# Power.net
KiCad netlist of a schematic drawn in Altium Designer
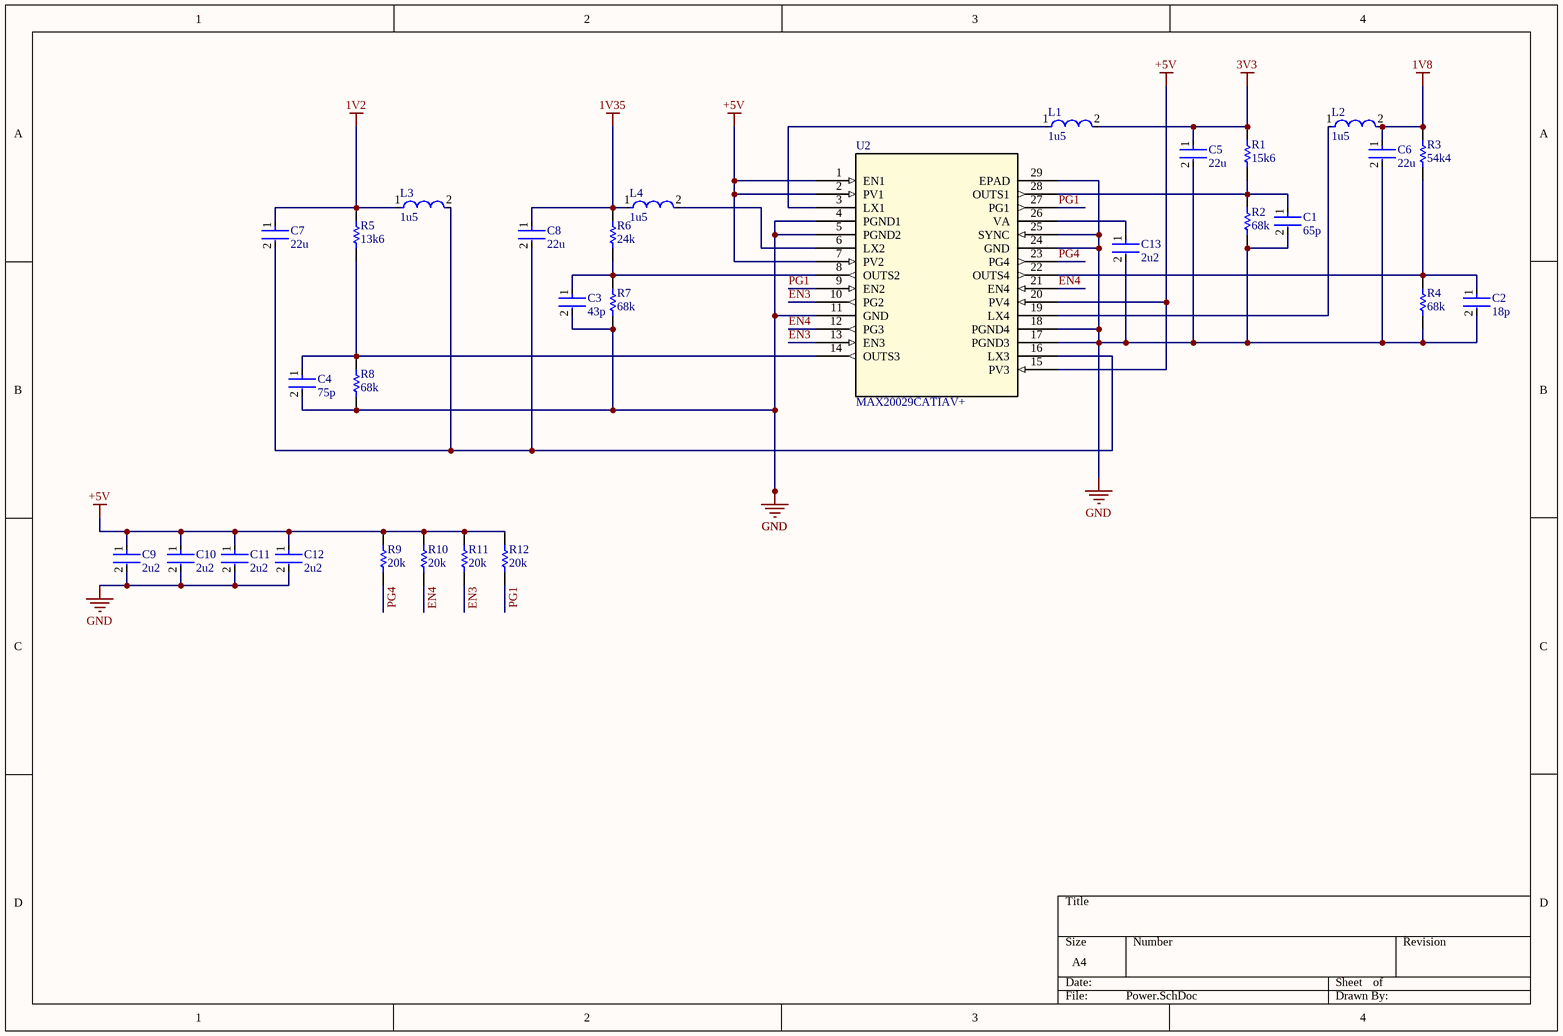
[diagram p0: Power.SchDoc]

(export (version "E")
  (design (tool "Eeschema 10.0.6"))
  (components
    (comp (ref "C1")
      (value "65p")
      (footprint "FP-C0603C-CF-MFG")
      (description "CAP CER 0.1UF 50V X7R 0603")
      (fields (field (name "TOLERANCE") "0.1") (field (name "MANUFACTURER") "KEMET"))
      (libsource (lib "Altium Content Vault") (part "b4654b650e69147ec39a6b967a45e02"))
    )
    (comp (ref "C2")
      (value "18p")
      (footprint "FP-C0603C-CF-MFG")
      (description "CAP CER 0.1UF 50V X7R 0603")
      (fields (field (name "TOLERANCE") "0.1") (field (name "MANUFACTURER") "KEMET"))
      (libsource (lib "Altium Content Vault") (part "b4654b650e69147ec39a6b967a45e02"))
    )
    (comp (ref "C3")
      (value "43p")
      (footprint "FP-C0603C-CF-MFG")
      (description "CAP CER 0.1UF 50V X7R 0603")
      (fields (field (name "TOLERANCE") "0.1") (field (name "MANUFACTURER") "KEMET"))
      (libsource (lib "Altium Content Vault") (part "b4654b650e69147ec39a6b967a45e02"))
    )
    (comp (ref "C4")
      (value "75p")
      (footprint "FP-C0603C-CF-MFG")
      (description "CAP CER 0.1UF 50V X7R 0603")
      (fields (field (name "TOLERANCE") "0.1") (field (name "MANUFACTURER") "KEMET"))
      (libsource (lib "Altium Content Vault") (part "b4654b650e69147ec39a6b967a45e02"))
    )
    (comp (ref "C5")
      (value "22u")
      (footprint "FP-CC0805-0_85-MFG")
      (description "CAP CER 0.1UF 50V X7R 0805")
      (fields (field (name "TOLERANCE") "0.1") (field (name "MANUFACTURER PART NUMBER") "CC0805KRX7R9BB104"))
      (libsource (lib "Altium Content Vault") (part "11868f565c42a9108669ba33697ecf6"))
    )
    (comp (ref "C6")
      (value "22u")
      (footprint "FP-CC0805-0_85-MFG")
      (description "CAP CER 0.1UF 50V X7R 0805")
      (fields (field (name "TOLERANCE") "0.1") (field (name "MANUFACTURER PART NUMBER") "CC0805KRX7R9BB104"))
      (libsource (lib "Altium Content Vault") (part "11868f565c42a9108669ba33697ecf6"))
    )
    (comp (ref "C7")
      (value "22u")
      (footprint "FP-CC0805-0_85-MFG")
      (description "CAP CER 0.1UF 50V X7R 0805")
      (fields (field (name "TOLERANCE") "0.1") (field (name "MANUFACTURER PART NUMBER") "CC0805KRX7R9BB104"))
      (libsource (lib "Altium Content Vault") (part "11868f565c42a9108669ba33697ecf6"))
    )
    (comp (ref "C8")
      (value "22u")
      (footprint "FP-CC0805-0_85-MFG")
      (description "CAP CER 0.1UF 50V X7R 0805")
      (fields (field (name "TOLERANCE") "0.1") (field (name "MANUFACTURER PART NUMBER") "CC0805KRX7R9BB104"))
      (libsource (lib "Altium Content Vault") (part "11868f565c42a9108669ba33697ecf6"))
    )
    (comp (ref "C9")
      (value "2u2")
      (footprint "FP-CC0805-0_85-MFG")
      (description "CAP CER 0.1UF 50V X7R 0805")
      (fields (field (name "TOLERANCE") "0.1") (field (name "MANUFACTURER PART NUMBER") "CC0805KRX7R9BB104"))
      (libsource (lib "Altium Content Vault") (part "11868f565c42a9108669ba33697ecf6"))
    )
    (comp (ref "C10")
      (value "2u2")
      (footprint "FP-CC0805-0_85-MFG")
      (description "CAP CER 0.1UF 50V X7R 0805")
      (fields (field (name "TOLERANCE") "0.1") (field (name "MANUFACTURER PART NUMBER") "CC0805KRX7R9BB104"))
      (libsource (lib "Altium Content Vault") (part "11868f565c42a9108669ba33697ecf6"))
    )
    (comp (ref "C11")
      (value "2u2")
      (footprint "FP-CC0805-0_85-MFG")
      (description "CAP CER 0.1UF 50V X7R 0805")
      (fields (field (name "TOLERANCE") "0.1") (field (name "MANUFACTURER PART NUMBER") "CC0805KRX7R9BB104"))
      (libsource (lib "Altium Content Vault") (part "11868f565c42a9108669ba33697ecf6"))
    )
    (comp (ref "C12")
      (value "2u2")
      (footprint "FP-CC0805-0_85-MFG")
      (description "CAP CER 0.1UF 50V X7R 0805")
      (fields (field (name "TOLERANCE") "0.1") (field (name "MANUFACTURER PART NUMBER") "CC0805KRX7R9BB104"))
      (libsource (lib "Altium Content Vault") (part "11868f565c42a9108669ba33697ecf6"))
    )
    (comp (ref "C13")
      (value "2u2")
      (footprint "FP-CC0805-0_85-MFG")
      (description "CAP CER 0.1UF 50V X7R 0805")
      (fields (field (name "TOLERANCE") "0.1") (field (name "MANUFACTURER PART NUMBER") "CC0805KRX7R9BB104"))
      (libsource (lib "Altium Content Vault") (part "11868f565c42a9108669ba33697ecf6"))
    )
    (comp (ref "L1")
      (value "1u5")
      (footprint "FP-LQM2HPN_G0-IPC_A")
      (description "FIXED IND 1UH 1.6A 55 MOHM SMD")
      (fields (field (name "TOLERANCE") "20%"))
      (libsource (lib "Altium Content Vault") (part "725321dda6339637d4d059423bc1c3c"))
    )
    (comp (ref "L2")
      (value "1u5")
      (footprint "FP-LQM2HPN_G0-IPC_A")
      (description "FIXED IND 1UH 1.6A 55 MOHM SMD")
      (fields (field (name "TOLERANCE") "20%"))
      (libsource (lib "Altium Content Vault") (part "725321dda6339637d4d059423bc1c3c"))
    )
    (comp (ref "L3")
      (value "1u5")
      (footprint "FP-LQM2HPN_G0-IPC_A")
      (description "FIXED IND 1UH 1.6A 55 MOHM SMD")
      (fields (field (name "TOLERANCE") "20%"))
      (libsource (lib "Altium Content Vault") (part "725321dda6339637d4d059423bc1c3c"))
    )
    (comp (ref "L4")
      (value "1u5")
      (footprint "FP-LQM2HPN_G0-IPC_A")
      (description "FIXED IND 1UH 1.6A 55 MOHM SMD")
      (fields (field (name "TOLERANCE") "20%"))
      (libsource (lib "Altium Content Vault") (part "725321dda6339637d4d059423bc1c3c"))
    )
    (comp (ref "R1")
      (value "15k6")
      (footprint "RESC1609X50X30NL8T20")
      (description "Chip Resistor, 10 KOhm, +/- 1%, 100 mW, -55 to 155 degC, 0603 (1608 Metric), RoHS, Tape and Reel")
      (fields (field (name "MANUFACTURER") "Vishay Semiconductor"))
      (libsource (lib "Altium Content Vault") (part "RES-2"))
    )
    (comp (ref "R2")
      (value "68k")
      (footprint "RESC1609X50X30NL8T20")
      (description "Chip Resistor, 10 KOhm, +/- 1%, 100 mW, -55 to 155 degC, 0603 (1608 Metric), RoHS, Tape and Reel")
      (fields (field (name "MANUFACTURER") "Vishay Semiconductor"))
      (libsource (lib "Altium Content Vault") (part "RES-2"))
    )
    (comp (ref "R3")
      (value "54k4")
      (footprint "RESC1609X50X30NL8T20")
      (description "Chip Resistor, 10 KOhm, +/- 1%, 100 mW, -55 to 155 degC, 0603 (1608 Metric), RoHS, Tape and Reel")
      (fields (field (name "MANUFACTURER") "Vishay Semiconductor"))
      (libsource (lib "Altium Content Vault") (part "RES-2"))
    )
    (comp (ref "R4")
      (value "68k")
      (footprint "RESC1609X50X30NL8T20")
      (description "Chip Resistor, 10 KOhm, +/- 1%, 100 mW, -55 to 155 degC, 0603 (1608 Metric), RoHS, Tape and Reel")
      (fields (field (name "MANUFACTURER") "Vishay Semiconductor"))
      (libsource (lib "Altium Content Vault") (part "RES-2"))
    )
    (comp (ref "R5")
      (value "13k6")
      (footprint "RESC1609X50X30NL8T20")
      (description "Chip Resistor, 10 KOhm, +/- 1%, 100 mW, -55 to 155 degC, 0603 (1608 Metric), RoHS, Tape and Reel")
      (fields (field (name "MANUFACTURER") "Vishay Semiconductor"))
      (libsource (lib "Altium Content Vault") (part "RES-2"))
    )
    (comp (ref "R6")
      (value "24k")
      (footprint "RESC1609X50X30NL8T20")
      (description "Chip Resistor, 10 KOhm, +/- 1%, 100 mW, -55 to 155 degC, 0603 (1608 Metric), RoHS, Tape and Reel")
      (fields (field (name "MANUFACTURER") "Vishay Semiconductor"))
      (libsource (lib "Altium Content Vault") (part "RES-2"))
    )
    (comp (ref "R7")
      (value "68k")
      (footprint "RESC1609X50X30NL8T20")
      (description "Chip Resistor, 10 KOhm, +/- 1%, 100 mW, -55 to 155 degC, 0603 (1608 Metric), RoHS, Tape and Reel")
      (fields (field (name "MANUFACTURER") "Vishay Semiconductor"))
      (libsource (lib "Altium Content Vault") (part "RES-2"))
    )
    (comp (ref "R8")
      (value "68k")
      (footprint "RESC1609X50X30NL8T20")
      (description "Chip Resistor, 10 KOhm, +/- 1%, 100 mW, -55 to 155 degC, 0603 (1608 Metric), RoHS, Tape and Reel")
      (fields (field (name "MANUFACTURER") "Vishay Semiconductor"))
      (libsource (lib "Altium Content Vault") (part "RES-2"))
    )
    (comp (ref "R9")
      (value "20k")
      (footprint "RESC1609X50X30NL8T20")
      (description "Chip Resistor, 10 KOhm, +/- 1%, 100 mW, -55 to 155 degC, 0603 (1608 Metric), RoHS, Tape and Reel")
      (fields (field (name "MANUFACTURER") "Vishay Semiconductor"))
      (libsource (lib "Altium Content Vault") (part "RES-2"))
    )
    (comp (ref "R10")
      (value "20k")
      (footprint "RESC1609X50X30NL8T20")
      (description "Chip Resistor, 10 KOhm, +/- 1%, 100 mW, -55 to 155 degC, 0603 (1608 Metric), RoHS, Tape and Reel")
      (fields (field (name "MANUFACTURER") "Vishay Semiconductor"))
      (libsource (lib "Altium Content Vault") (part "RES-2"))
    )
    (comp (ref "R11")
      (value "20k")
      (footprint "RESC1609X50X30NL8T20")
      (description "Chip Resistor, 10 KOhm, +/- 1%, 100 mW, -55 to 155 degC, 0603 (1608 Metric), RoHS, Tape and Reel")
      (fields (field (name "MANUFACTURER") "Vishay Semiconductor"))
      (libsource (lib "Altium Content Vault") (part "RES-2"))
    )
    (comp (ref "R12")
      (value "20k")
      (footprint "RESC1609X50X30NL8T20")
      (description "Chip Resistor, 10 KOhm, +/- 1%, 100 mW, -55 to 155 degC, 0603 (1608 Metric), RoHS, Tape and Reel")
      (fields (field (name "MANUFACTURER") "Vishay Semiconductor"))
      (libsource (lib "Altium Content Vault") (part "RES-2"))
    )
    (comp (ref "U2")
      (value "MAX20029CATIAV+")
      (footprint "QUADBUCK QFN28")
      (description "No Description Available")
      (libsource (lib "Master") (part "MAX20029CATIAV+"))
    )
  )
  (nets
    (net (code "1") (name "+5V") (class "Default")
      (node (ref "C10") (pin "1") (pinfunction "1_1") (pintype "passive"))
      (node (ref "C11") (pin "1") (pinfunction "1_1") (pintype "passive"))
      (node (ref "C12") (pin "1") (pinfunction "1_1") (pintype "passive"))
      (node (ref "C9") (pin "1") (pinfunction "1_1") (pintype "passive"))
      (node (ref "R10") (pin "1") (pinfunction "1_1") (pintype "passive"))
      (node (ref "R11") (pin "1") (pinfunction "1_1") (pintype "passive"))
      (node (ref "R12") (pin "1") (pinfunction "1_1") (pintype "passive"))
      (node (ref "R9") (pin "1") (pinfunction "1_1") (pintype "passive"))
      (node (ref "U2") (pin "1") (pinfunction "EN1_1") (pintype "input"))
      (node (ref "U2") (pin "15") (pinfunction "PV3_15") (pintype "input"))
      (node (ref "U2") (pin "2") (pinfunction "PV1_2") (pintype "input"))
      (node (ref "U2") (pin "20") (pinfunction "PV4_20") (pintype "input"))
      (node (ref "U2") (pin "7") (pinfunction "PV2_7") (pintype "input"))
    )
    (net (code "2") (name "/EN3") (class "Default")
      (node (ref "R11") (pin "2") (pinfunction "2_2") (pintype "passive"))
      (node (ref "U2") (pin "10") (pinfunction "PG2_10") (pintype "output"))
      (node (ref "U2") (pin "13") (pinfunction "EN3_13") (pintype "input"))
    )
    (net (code "3") (name "/EN4") (class "Default")
      (node (ref "R10") (pin "2") (pinfunction "2_2") (pintype "passive"))
      (node (ref "U2") (pin "12") (pinfunction "PG3_12") (pintype "output"))
      (node (ref "U2") (pin "21") (pinfunction "EN4_21") (pintype "input"))
    )
    (net (code "4") (name "/PG1") (class "Default")
      (node (ref "R12") (pin "2") (pinfunction "2_2") (pintype "passive"))
      (node (ref "U2") (pin "27") (pinfunction "PG1_27") (pintype "output"))
      (node (ref "U2") (pin "9") (pinfunction "EN2_9") (pintype "input"))
    )
    (net (code "5") (name "/PG4") (class "Default")
      (node (ref "R9") (pin "2") (pinfunction "2_2") (pintype "passive"))
      (node (ref "U2") (pin "23") (pinfunction "PG4_23") (pintype "output"))
    )
    (net (code "6") (name "1V2") (class "Default")
      (node (ref "C7") (pin "1") (pinfunction "1_1") (pintype "passive"))
      (node (ref "L3") (pin "1") (pinfunction "1_1") (pintype "passive"))
      (node (ref "R5") (pin "1") (pinfunction "1_1") (pintype "passive"))
    )
    (net (code "7") (name "1V8") (class "Default")
      (node (ref "C6") (pin "1") (pinfunction "1_1") (pintype "passive"))
      (node (ref "L2") (pin "2") (pinfunction "2_2") (pintype "passive"))
      (node (ref "R3") (pin "1") (pinfunction "1_1") (pintype "passive"))
    )
    (net (code "8") (name "1V35") (class "Default")
      (node (ref "C8") (pin "1") (pinfunction "1_1") (pintype "passive"))
      (node (ref "L4") (pin "1") (pinfunction "1_1") (pintype "passive"))
      (node (ref "R6") (pin "1") (pinfunction "1_1") (pintype "passive"))
    )
    (net (code "9") (name "3V3") (class "Default")
      (node (ref "C5") (pin "1") (pinfunction "1_1") (pintype "passive"))
      (node (ref "L1") (pin "2") (pinfunction "2_2") (pintype "passive"))
      (node (ref "R1") (pin "1") (pinfunction "1_1") (pintype "passive"))
    )
    (net (code "10") (name "GND") (class "Default")
      (node (ref "C1") (pin "2") (pinfunction "2_2") (pintype "passive"))
      (node (ref "C10") (pin "2") (pinfunction "2_2") (pintype "passive"))
      (node (ref "C11") (pin "2") (pinfunction "2_2") (pintype "passive"))
      (node (ref "C12") (pin "2") (pinfunction "2_2") (pintype "passive"))
      (node (ref "C13") (pin "2") (pinfunction "2_2") (pintype "passive"))
      (node (ref "C2") (pin "2") (pinfunction "2_2") (pintype "passive"))
      (node (ref "C3") (pin "2") (pinfunction "2_2") (pintype "passive"))
      (node (ref "C4") (pin "2") (pinfunction "2_2") (pintype "passive"))
      (node (ref "C5") (pin "2") (pinfunction "2_2") (pintype "passive"))
      (node (ref "C6") (pin "2") (pinfunction "2_2") (pintype "passive"))
      (node (ref "C9") (pin "2") (pinfunction "2_2") (pintype "passive"))
      (node (ref "R2") (pin "2") (pinfunction "2_2") (pintype "passive"))
      (node (ref "R4") (pin "2") (pinfunction "2_2") (pintype "passive"))
      (node (ref "R7") (pin "2") (pinfunction "2_2") (pintype "passive"))
      (node (ref "R8") (pin "2") (pinfunction "2_2") (pintype "passive"))
      (node (ref "U2") (pin "11") (pinfunction "GND_11") (pintype "power_in"))
      (node (ref "U2") (pin "17") (pinfunction "PGND3_17") (pintype "power_in"))
      (node (ref "U2") (pin "18") (pinfunction "PGND4_18") (pintype "power_in"))
      (node (ref "U2") (pin "24") (pinfunction "GND_24") (pintype "power_in"))
      (node (ref "U2") (pin "25") (pinfunction "SYNC_25") (pintype "input"))
      (node (ref "U2") (pin "29") (pinfunction "EPAD_29") (pintype "passive"))
      (node (ref "U2") (pin "4") (pinfunction "PGND1_4") (pintype "power_in"))
      (node (ref "U2") (pin "5") (pinfunction "PGND2_5") (pintype "power_in"))
    )
    (net (code "11") (name "Net-(U2-LX1)") (class "Default")
      (node (ref "L1") (pin "1") (pinfunction "1_1") (pintype "passive"))
      (node (ref "U2") (pin "3") (pinfunction "LX1_3") (pintype "passive"))
    )
    (net (code "12") (name "Net-(U2-LX2)") (class "Default")
      (node (ref "L4") (pin "2") (pinfunction "2_2") (pintype "passive"))
      (node (ref "U2") (pin "6") (pinfunction "LX2_6") (pintype "passive"))
    )
    (net (code "13") (name "Net-(U2-LX3)") (class "Default")
      (node (ref "C7") (pin "2") (pinfunction "2_2") (pintype "passive"))
      (node (ref "C8") (pin "2") (pinfunction "2_2") (pintype "passive"))
      (node (ref "L3") (pin "2") (pinfunction "2_2") (pintype "passive"))
      (node (ref "U2") (pin "16") (pinfunction "LX3_16") (pintype "passive"))
    )
    (net (code "14") (name "Net-(U2-LX4)") (class "Default")
      (node (ref "L2") (pin "1") (pinfunction "1_1") (pintype "passive"))
      (node (ref "U2") (pin "19") (pinfunction "LX4_19") (pintype "passive"))
    )
    (net (code "15") (name "Net-(U2-OUTS1)") (class "Default")
      (node (ref "C1") (pin "1") (pinfunction "1_1") (pintype "passive"))
      (node (ref "R1") (pin "2") (pinfunction "2_2") (pintype "passive"))
      (node (ref "R2") (pin "1") (pinfunction "1_1") (pintype "passive"))
      (node (ref "U2") (pin "28") (pinfunction "OUTS1_28") (pintype "output"))
    )
    (net (code "16") (name "Net-(U2-OUTS2)") (class "Default")
      (node (ref "C3") (pin "1") (pinfunction "1_1") (pintype "passive"))
      (node (ref "R6") (pin "2") (pinfunction "2_2") (pintype "passive"))
      (node (ref "R7") (pin "1") (pinfunction "1_1") (pintype "passive"))
      (node (ref "U2") (pin "8") (pinfunction "OUTS2_8") (pintype "output"))
    )
    (net (code "17") (name "Net-(U2-OUTS3)") (class "Default")
      (node (ref "C4") (pin "1") (pinfunction "1_1") (pintype "passive"))
      (node (ref "R5") (pin "2") (pinfunction "2_2") (pintype "passive"))
      (node (ref "R8") (pin "1") (pinfunction "1_1") (pintype "passive"))
      (node (ref "U2") (pin "14") (pinfunction "OUTS3_14") (pintype "output"))
    )
    (net (code "18") (name "Net-(U2-OUTS4)") (class "Default")
      (node (ref "C2") (pin "1") (pinfunction "1_1") (pintype "passive"))
      (node (ref "R3") (pin "2") (pinfunction "2_2") (pintype "passive"))
      (node (ref "R4") (pin "1") (pinfunction "1_1") (pintype "passive"))
      (node (ref "U2") (pin "22") (pinfunction "OUTS4_22") (pintype "output"))
    )
    (net (code "19") (name "Net-(U2-VA)") (class "Default")
      (node (ref "C13") (pin "1") (pinfunction "1_1") (pintype "passive"))
      (node (ref "U2") (pin "26") (pinfunction "VA_26") (pintype "power_in"))
    )
  )
)
